# Program_Counter.net
KiCad netlist of a schematic drawn in EAGLE
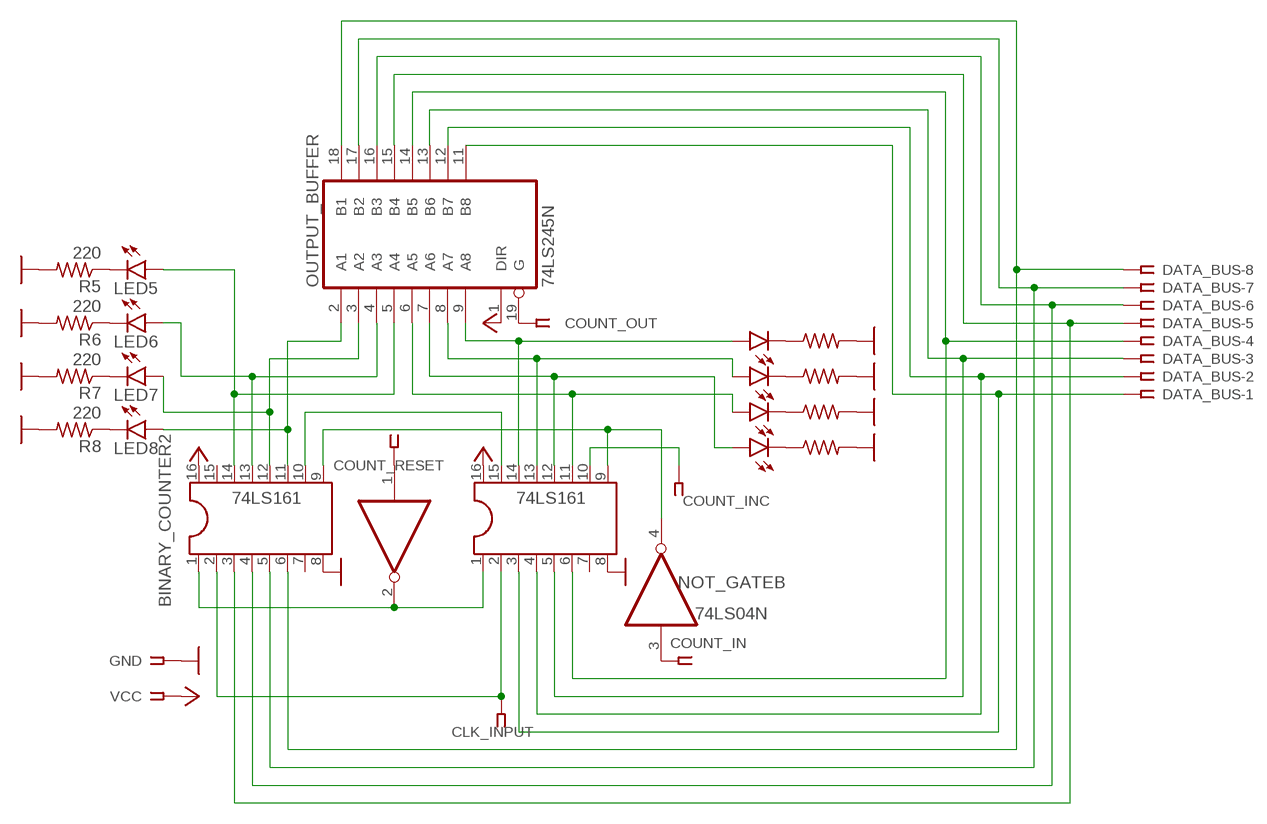
[diagram p0: schematic, sheet 1]

(export (version "E")
  (design (tool "Eeschema 10.0.6"))
  (components
    (comp (ref "BINARY_COUNTER")
      (value "74LS161")
      (footprint "eagle-import:DIL16")
      (libsource (lib "eagle-import") (part "DIL16"))
    )
    (comp (ref "BINARY_COUNTER2")
      (value "74LS161")
      (footprint "eagle-import:DIL16")
      (libsource (lib "eagle-import") (part "DIL16"))
    )
    (comp (ref "CLK_INPUT")
      (value "SSW-101-02-G-S-RA")
      (footprint "eagle-import:SSW-101-02-G-S-RA")
      (fields (field (name "MF") "Samtec Inc."))
      (libsource (lib "eagle-import") (part "SSW-101-02-G-S-RA"))
    )
    (comp (ref "COUNT_IN")
      (value "SSW-101-02-G-S-RA")
      (footprint "eagle-import:SSW-101-02-G-S-RA")
      (fields (field (name "MF") "Samtec Inc."))
      (libsource (lib "eagle-import") (part "SSW-101-02-G-S-RA"))
    )
    (comp (ref "COUNT_INC")
      (value "SSW-101-02-G-S-RA")
      (footprint "eagle-import:SSW-101-02-G-S-RA")
      (fields (field (name "MF") "Samtec Inc."))
      (libsource (lib "eagle-import") (part "SSW-101-02-G-S-RA"))
    )
    (comp (ref "COUNT_OUT")
      (value "SSW-101-02-G-S-RA")
      (footprint "eagle-import:SSW-101-02-G-S-RA")
      (fields (field (name "MF") "Samtec Inc."))
      (libsource (lib "eagle-import") (part "SSW-101-02-G-S-RA"))
    )
    (comp (ref "COUNT_RESET")
      (value "SSW-101-02-G-S-RA")
      (footprint "eagle-import:SSW-101-02-G-S-RA")
      (fields (field (name "MF") "Samtec Inc."))
      (libsource (lib "eagle-import") (part "SSW-101-02-G-S-RA"))
    )
    (comp (ref "DATA_BUS")
      (value "SSW-108-02-G-S")
      (footprint "eagle-import:SSW-108-02-G-S")
      (fields (field (name "MF") "Samtec Inc."))
      (libsource (lib "eagle-import") (part "SSW-108-02-G-S"))
    )
    (comp (ref "GND")
      (value "SSW-101-02-G-S-RA")
      (footprint "eagle-import:SSW-101-02-G-S-RA")
      (fields (field (name "MF") "Samtec Inc."))
      (libsource (lib "eagle-import") (part "SSW-101-02-G-S-RA"))
    )
    (comp (ref "LED1")
      (value "LED5MM")
      (footprint "eagle-import:LED5MM")
      (libsource (lib "eagle-import") (part "LED5MM"))
    )
    (comp (ref "LED2")
      (value "LED5MM")
      (footprint "eagle-import:LED5MM")
      (libsource (lib "eagle-import") (part "LED5MM"))
    )
    (comp (ref "LED3")
      (value "LED5MM")
      (footprint "eagle-import:LED5MM")
      (libsource (lib "eagle-import") (part "LED5MM"))
    )
    (comp (ref "LED4")
      (value "LED5MM")
      (footprint "eagle-import:LED5MM")
      (libsource (lib "eagle-import") (part "LED5MM"))
    )
    (comp (ref "LED5")
      (value "LED5MM")
      (footprint "eagle-import:LED5MM")
      (libsource (lib "eagle-import") (part "LED5MM"))
    )
    (comp (ref "LED6")
      (value "LED5MM")
      (footprint "eagle-import:LED5MM")
      (libsource (lib "eagle-import") (part "LED5MM"))
    )
    (comp (ref "LED7")
      (value "LED5MM")
      (footprint "eagle-import:LED5MM")
      (libsource (lib "eagle-import") (part "LED5MM"))
    )
    (comp (ref "LED8")
      (value "LED5MM")
      (footprint "eagle-import:LED5MM")
      (libsource (lib "eagle-import") (part "LED5MM"))
    )
    (comp (ref "NOT_GATE")
      (value "74LS04N")
      (footprint "eagle-import:DIL14")
      (libsource (lib "eagle-import") (part "7404NLS"))
    )
    (comp (ref "OUTPUT_BUFFER")
      (value "74LS245N")
      (footprint "eagle-import:DIL20")
      (libsource (lib "eagle-import") (part "74245NLS"))
    )
    (comp (ref "R1")
      (value "220")
      (footprint "eagle-import:0204_7")
      (libsource (lib "eagle-import") (part "R-US_0204/7"))
    )
    (comp (ref "R2")
      (value "220")
      (footprint "eagle-import:0204_7")
      (libsource (lib "eagle-import") (part "R-US_0204/7"))
    )
    (comp (ref "R3")
      (value "220")
      (footprint "eagle-import:0204_7")
      (libsource (lib "eagle-import") (part "R-US_0204/7"))
    )
    (comp (ref "R4")
      (value "220")
      (footprint "eagle-import:0204_7")
      (libsource (lib "eagle-import") (part "R-US_0204/7"))
    )
    (comp (ref "R5")
      (value "220")
      (footprint "eagle-import:0204_7")
      (libsource (lib "eagle-import") (part "R-US_0204/7"))
    )
    (comp (ref "R6")
      (value "220")
      (footprint "eagle-import:0204_7")
      (libsource (lib "eagle-import") (part "R-US_0204/7"))
    )
    (comp (ref "R7")
      (value "220")
      (footprint "eagle-import:0204_7")
      (libsource (lib "eagle-import") (part "R-US_0204/7"))
    )
    (comp (ref "R8")
      (value "220")
      (footprint "eagle-import:0204_7")
      (libsource (lib "eagle-import") (part "R-US_0204/7"))
    )
    (comp (ref "VCC")
      (value "SSW-101-02-G-S-RA")
      (footprint "eagle-import:SSW-101-02-G-S-RA")
      (fields (field (name "MF") "Samtec Inc."))
      (libsource (lib "eagle-import") (part "SSW-101-02-G-S-RA"))
    )
  )
  (nets
    (net (code "1") (name "GND") (class "Default")
      (node (ref "BINARY_COUNTER") (pin "8") (pinfunction "8_8") (pintype "passive"))
      (node (ref "BINARY_COUNTER2") (pin "8") (pinfunction "8_8") (pintype "passive"))
      (node (ref "GND") (pin "1") (pinfunction "1_1") (pintype "passive"))
      (node (ref "R1") (pin "2") (pinfunction "2_2") (pintype "passive"))
      (node (ref "R2") (pin "2") (pinfunction "2_2") (pintype "passive"))
      (node (ref "R3") (pin "2") (pinfunction "2_2") (pintype "passive"))
      (node (ref "R4") (pin "2") (pinfunction "2_2") (pintype "passive"))
      (node (ref "R5") (pin "2") (pinfunction "2_2") (pintype "passive"))
      (node (ref "R6") (pin "2") (pinfunction "2_2") (pintype "passive"))
      (node (ref "R7") (pin "2") (pinfunction "2_2") (pintype "passive"))
      (node (ref "R8") (pin "2") (pinfunction "2_2") (pintype "passive"))
    )
    (net (code "2") (name "Net-(BINARY_COUNTER-Pad2)") (class "Default")
      (node (ref "BINARY_COUNTER") (pin "2") (pinfunction "2_2") (pintype "passive"))
      (node (ref "BINARY_COUNTER2") (pin "2") (pinfunction "2_2") (pintype "passive"))
      (node (ref "CLK_INPUT") (pin "1") (pinfunction "1_1") (pintype "passive"))
    )
    (net (code "3") (name "Net-(BINARY_COUNTER-Pad10)") (class "Default")
      (node (ref "BINARY_COUNTER") (pin "10") (pinfunction "10_10") (pintype "passive"))
      (node (ref "COUNT_INC") (pin "1") (pinfunction "1_1") (pintype "passive"))
    )
    (net (code "4") (name "Net-(BINARY_COUNTER-Pad15)") (class "Default")
      (node (ref "BINARY_COUNTER") (pin "15") (pinfunction "15_15") (pintype "passive"))
      (node (ref "BINARY_COUNTER2") (pin "10") (pinfunction "10_10") (pintype "passive"))
    )
    (net (code "5") (name "Net-(DATA_BUSB-1)") (class "Default")
      (node (ref "BINARY_COUNTER") (pin "4") (pinfunction "4_4") (pintype "passive"))
      (node (ref "DATA_BUS") (pin "2") (pinfunction "1_2") (pintype "passive"))
      (node (ref "OUTPUT_BUFFER") (pin "12") (pinfunction "B7_12") (pintype "bidirectional"))
    )
    (net (code "6") (name "Net-(DATA_BUSC-1)") (class "Default")
      (node (ref "BINARY_COUNTER") (pin "5") (pinfunction "5_5") (pintype "passive"))
      (node (ref "DATA_BUS") (pin "3") (pinfunction "1_3") (pintype "passive"))
      (node (ref "OUTPUT_BUFFER") (pin "13") (pinfunction "B6_13") (pintype "bidirectional"))
    )
    (net (code "7") (name "Net-(DATA_BUSD-1)") (class "Default")
      (node (ref "BINARY_COUNTER") (pin "6") (pinfunction "6_6") (pintype "passive"))
      (node (ref "DATA_BUS") (pin "4") (pinfunction "1_4") (pintype "passive"))
      (node (ref "OUTPUT_BUFFER") (pin "14") (pinfunction "B5_14") (pintype "bidirectional"))
    )
    (net (code "8") (name "Net-(DATA_BUSE-1)") (class "Default")
      (node (ref "BINARY_COUNTER2") (pin "3") (pinfunction "3_3") (pintype "passive"))
      (node (ref "DATA_BUS") (pin "5") (pinfunction "1_5") (pintype "passive"))
      (node (ref "OUTPUT_BUFFER") (pin "15") (pinfunction "B4_15") (pintype "bidirectional"))
    )
    (net (code "9") (name "Net-(DATA_BUSF-1)") (class "Default")
      (node (ref "BINARY_COUNTER2") (pin "4") (pinfunction "4_4") (pintype "passive"))
      (node (ref "DATA_BUS") (pin "6") (pinfunction "1_6") (pintype "passive"))
      (node (ref "OUTPUT_BUFFER") (pin "16") (pinfunction "B3_16") (pintype "bidirectional"))
    )
    (net (code "10") (name "Net-(DATA_BUSG-1)") (class "Default")
      (node (ref "BINARY_COUNTER2") (pin "5") (pinfunction "5_5") (pintype "passive"))
      (node (ref "DATA_BUS") (pin "7") (pinfunction "1_7") (pintype "passive"))
      (node (ref "OUTPUT_BUFFER") (pin "17") (pinfunction "B2_17") (pintype "bidirectional"))
    )
    (net (code "11") (name "Net-(DATA_BUSH-1)") (class "Default")
      (node (ref "BINARY_COUNTER2") (pin "6") (pinfunction "6_6") (pintype "passive"))
      (node (ref "DATA_BUS") (pin "8") (pinfunction "1_8") (pintype "passive"))
      (node (ref "OUTPUT_BUFFER") (pin "18") (pinfunction "B1_18") (pintype "bidirectional"))
    )
    (net (code "12") (name "Net-(LED1-C)") (class "Default")
      (node (ref "LED1") (pin "K") (pinfunction "C_K") (pintype "passive"))
      (node (ref "R1") (pin "1") (pinfunction "1_1") (pintype "passive"))
    )
    (net (code "13") (name "Net-(LED2-C)") (class "Default")
      (node (ref "LED2") (pin "K") (pinfunction "C_K") (pintype "passive"))
      (node (ref "R2") (pin "1") (pinfunction "1_1") (pintype "passive"))
    )
    (net (code "14") (name "Net-(LED3-C)") (class "Default")
      (node (ref "LED3") (pin "K") (pinfunction "C_K") (pintype "passive"))
      (node (ref "R3") (pin "1") (pinfunction "1_1") (pintype "passive"))
    )
    (net (code "15") (name "Net-(LED4-C)") (class "Default")
      (node (ref "LED4") (pin "K") (pinfunction "C_K") (pintype "passive"))
      (node (ref "R4") (pin "1") (pinfunction "1_1") (pintype "passive"))
    )
    (net (code "16") (name "Net-(LED5-C)") (class "Default")
      (node (ref "LED5") (pin "K") (pinfunction "C_K") (pintype "passive"))
      (node (ref "R5") (pin "1") (pinfunction "1_1") (pintype "passive"))
    )
    (net (code "17") (name "Net-(LED6-C)") (class "Default")
      (node (ref "LED6") (pin "K") (pinfunction "C_K") (pintype "passive"))
      (node (ref "R6") (pin "1") (pinfunction "1_1") (pintype "passive"))
    )
    (net (code "18") (name "Net-(LED7-C)") (class "Default")
      (node (ref "LED7") (pin "K") (pinfunction "C_K") (pintype "passive"))
      (node (ref "R7") (pin "1") (pinfunction "1_1") (pintype "passive"))
    )
    (net (code "19") (name "Net-(LED8-C)") (class "Default")
      (node (ref "LED8") (pin "K") (pinfunction "C_K") (pintype "passive"))
      (node (ref "R8") (pin "1") (pinfunction "1_1") (pintype "passive"))
    )
    (net (code "20") (name "Net-(NOT_GATEA-I)") (class "Default")
      (node (ref "COUNT_RESET") (pin "1") (pinfunction "1_1") (pintype "passive"))
      (node (ref "NOT_GATE") (pin "1") (pinfunction "I_1") (pintype "input"))
    )
    (net (code "21") (name "Net-(NOT_GATEA-O)") (class "Default")
      (node (ref "BINARY_COUNTER") (pin "1") (pinfunction "1_1") (pintype "passive"))
      (node (ref "BINARY_COUNTER2") (pin "1") (pinfunction "1_1") (pintype "passive"))
      (node (ref "NOT_GATE") (pin "2") (pinfunction "O_2") (pintype "output"))
    )
    (net (code "22") (name "Net-(NOT_GATEB-I)") (class "Default")
      (node (ref "COUNT_IN") (pin "1") (pinfunction "1_1") (pintype "passive"))
      (node (ref "NOT_GATE") (pin "3") (pinfunction "I_3") (pintype "input"))
    )
    (net (code "23") (name "Net-(NOT_GATEB-O)") (class "Default")
      (node (ref "BINARY_COUNTER") (pin "9") (pinfunction "9_9") (pintype "passive"))
      (node (ref "BINARY_COUNTER2") (pin "9") (pinfunction "9_9") (pintype "passive"))
      (node (ref "NOT_GATE") (pin "4") (pinfunction "O_4") (pintype "output"))
    )
    (net (code "24") (name "Net-(OUTPUT_BUFFERA-A1)") (class "Default")
      (node (ref "BINARY_COUNTER2") (pin "11") (pinfunction "11_11") (pintype "passive"))
      (node (ref "LED8") (pin "A") (pinfunction "A_A") (pintype "passive"))
      (node (ref "OUTPUT_BUFFER") (pin "2") (pinfunction "A1_2") (pintype "bidirectional"))
    )
    (net (code "25") (name "Net-(OUTPUT_BUFFERA-A2)") (class "Default")
      (node (ref "BINARY_COUNTER2") (pin "12") (pinfunction "12_12") (pintype "passive"))
      (node (ref "LED7") (pin "A") (pinfunction "A_A") (pintype "passive"))
      (node (ref "OUTPUT_BUFFER") (pin "3") (pinfunction "A2_3") (pintype "bidirectional"))
    )
    (net (code "26") (name "Net-(OUTPUT_BUFFERA-A3)") (class "Default")
      (node (ref "BINARY_COUNTER2") (pin "13") (pinfunction "13_13") (pintype "passive"))
      (node (ref "LED6") (pin "A") (pinfunction "A_A") (pintype "passive"))
      (node (ref "OUTPUT_BUFFER") (pin "4") (pinfunction "A3_4") (pintype "bidirectional"))
    )
    (net (code "27") (name "Net-(OUTPUT_BUFFERA-A4)") (class "Default")
      (node (ref "BINARY_COUNTER2") (pin "14") (pinfunction "14_14") (pintype "passive"))
      (node (ref "LED5") (pin "A") (pinfunction "A_A") (pintype "passive"))
      (node (ref "OUTPUT_BUFFER") (pin "5") (pinfunction "A4_5") (pintype "bidirectional"))
    )
    (net (code "28") (name "Net-(OUTPUT_BUFFERA-A5)") (class "Default")
      (node (ref "BINARY_COUNTER") (pin "11") (pinfunction "11_11") (pintype "passive"))
      (node (ref "LED4") (pin "A") (pinfunction "A_A") (pintype "passive"))
      (node (ref "OUTPUT_BUFFER") (pin "6") (pinfunction "A5_6") (pintype "bidirectional"))
    )
    (net (code "29") (name "Net-(OUTPUT_BUFFERA-A6)") (class "Default")
      (node (ref "BINARY_COUNTER") (pin "12") (pinfunction "12_12") (pintype "passive"))
      (node (ref "LED3") (pin "A") (pinfunction "A_A") (pintype "passive"))
      (node (ref "OUTPUT_BUFFER") (pin "7") (pinfunction "A6_7") (pintype "bidirectional"))
    )
    (net (code "30") (name "Net-(OUTPUT_BUFFERA-A7)") (class "Default")
      (node (ref "BINARY_COUNTER") (pin "13") (pinfunction "13_13") (pintype "passive"))
      (node (ref "LED2") (pin "A") (pinfunction "A_A") (pintype "passive"))
      (node (ref "OUTPUT_BUFFER") (pin "8") (pinfunction "A7_8") (pintype "bidirectional"))
    )
    (net (code "31") (name "Net-(OUTPUT_BUFFERA-A8)") (class "Default")
      (node (ref "BINARY_COUNTER") (pin "14") (pinfunction "14_14") (pintype "passive"))
      (node (ref "LED1") (pin "A") (pinfunction "A_A") (pintype "passive"))
      (node (ref "OUTPUT_BUFFER") (pin "9") (pinfunction "A8_9") (pintype "bidirectional"))
    )
    (net (code "32") (name "Net-(OUTPUT_BUFFERA-B8)") (class "Default")
      (node (ref "BINARY_COUNTER") (pin "3") (pinfunction "3_3") (pintype "passive"))
      (node (ref "DATA_BUS") (pin "1") (pinfunction "1_1") (pintype "passive"))
      (node (ref "OUTPUT_BUFFER") (pin "11") (pinfunction "B8_11") (pintype "bidirectional"))
    )
    (net (code "33") (name "Net-(OUTPUT_BUFFERA-G)") (class "Default")
      (node (ref "COUNT_OUT") (pin "1") (pinfunction "1_1") (pintype "passive"))
      (node (ref "OUTPUT_BUFFER") (pin "19") (pinfunction "G_19") (pintype "input"))
    )
    (net (code "34") (name "VCC") (class "Default")
      (node (ref "BINARY_COUNTER") (pin "16") (pinfunction "16_16") (pintype "passive"))
      (node (ref "BINARY_COUNTER2") (pin "16") (pinfunction "16_16") (pintype "passive"))
      (node (ref "OUTPUT_BUFFER") (pin "1") (pinfunction "DIR_1") (pintype "input"))
      (node (ref "VCC") (pin "1") (pinfunction "1_1") (pintype "passive"))
    )
    (net (code "35") (name "unconnected-(BINARY_COUNTER-Pad7)") (class "Default")
      (node (ref "BINARY_COUNTER") (pin "7") (pinfunction "7_7") (pintype "passive"))
    )
    (net (code "36") (name "unconnected-(BINARY_COUNTER2-Pad7)") (class "Default")
      (node (ref "BINARY_COUNTER2") (pin "7") (pinfunction "7_7") (pintype "passive"))
    )
    (net (code "37") (name "unconnected-(BINARY_COUNTER2-Pad15)") (class "Default")
      (node (ref "BINARY_COUNTER2") (pin "15") (pinfunction "15_15") (pintype "passive"))
    )
  )
)
